# T01_Synth_Glove_v3_1.net
KiCad netlist of a schematic drawn in EAGLE
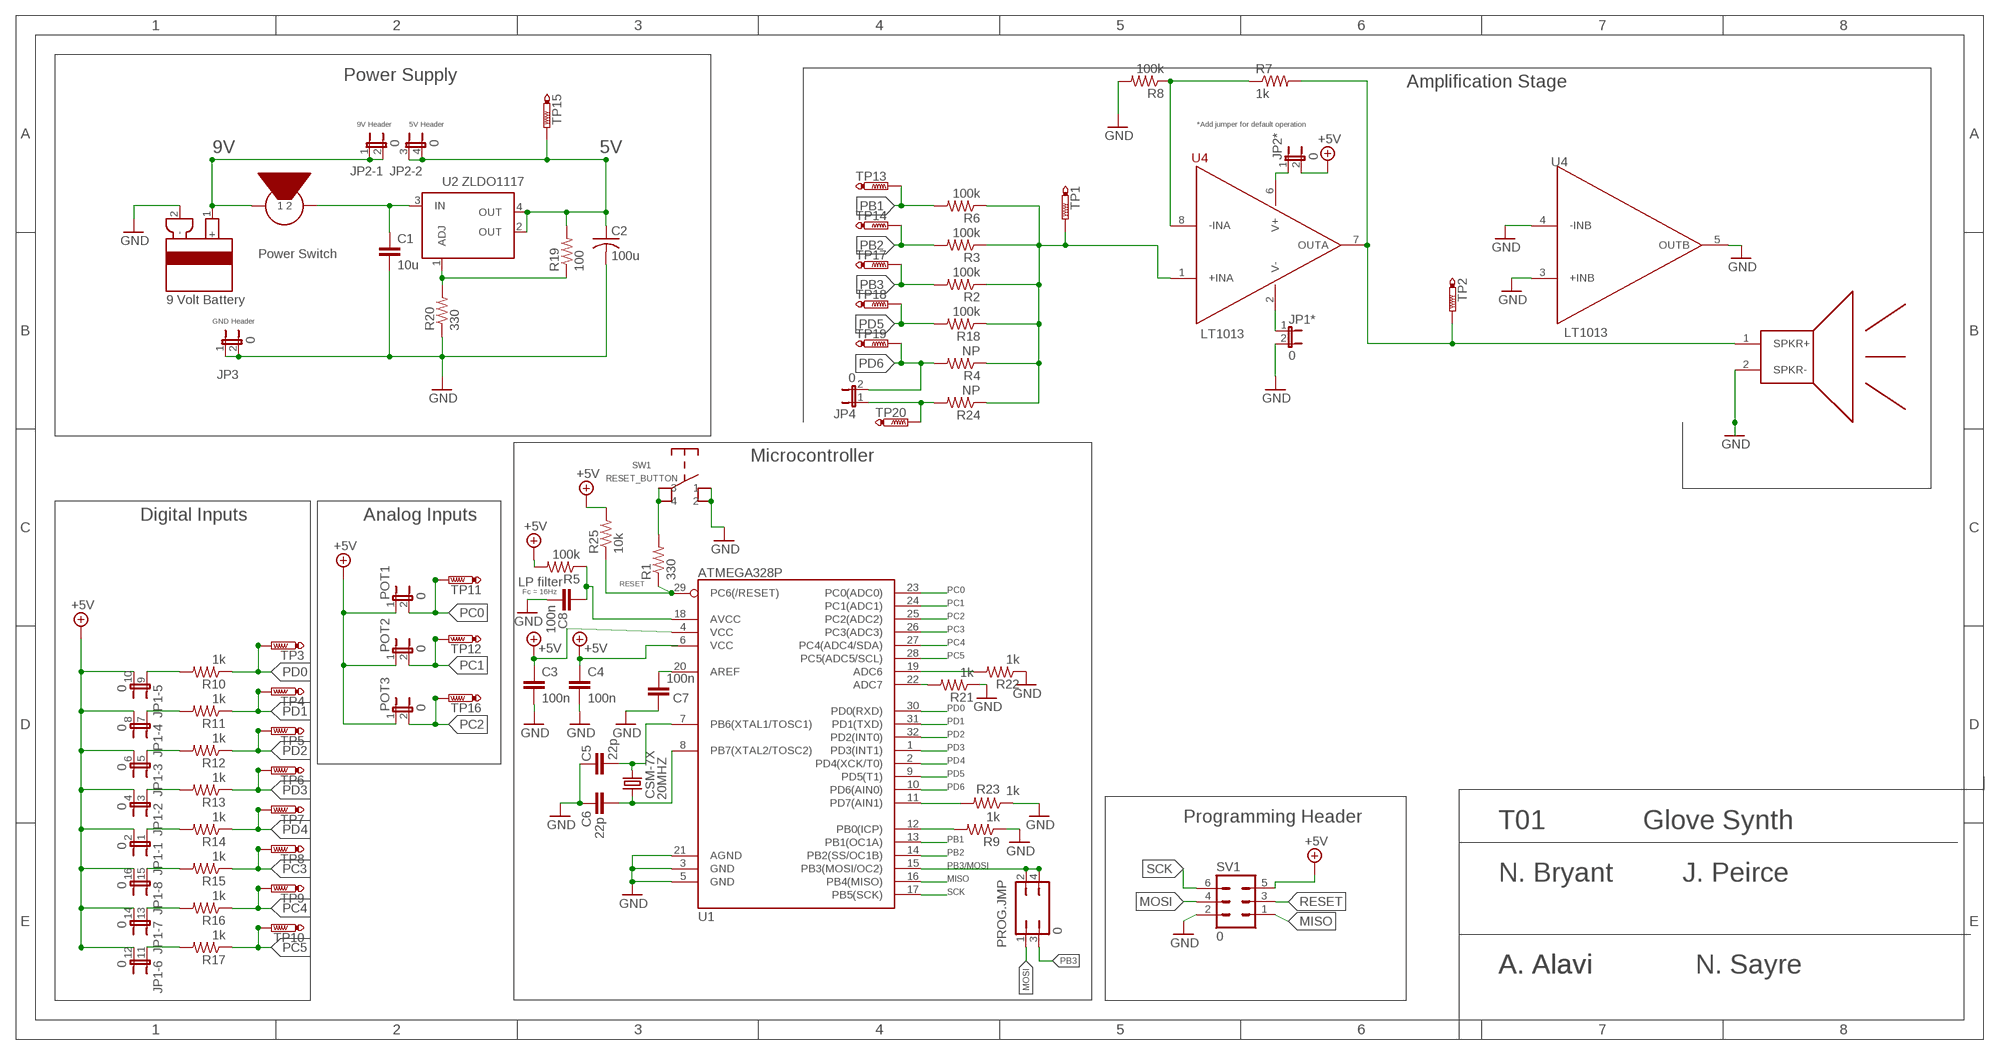
[diagram p0: schematic, sheet 1]

(export (version "E")
  (design (tool "Eeschema 10.0.6"))
  (components
    (comp (ref "20MHZ")
      (value "CSM-7X")
      (footprint "eagle-import:CSM-7X-DU")
      (libsource (lib "eagle-import") (part "CSM-7X-DU"))
    )
    (comp (ref "C1")
      (value "10u")
      (footprint "eagle-import:0603-CAP")
      (libsource (lib "eagle-import") (part "CAP0603-CAP"))
    )
    (comp (ref "C2")
      (value "100u")
      (footprint "eagle-import:C075-042X103")
      (libsource (lib "eagle-import") (part "C-US075-042X103"))
    )
    (comp (ref "C3")
      (value "100n")
      (footprint "eagle-import:0603-CAP")
      (libsource (lib "eagle-import") (part "CAP0603-CAP"))
    )
    (comp (ref "C4")
      (value "100n")
      (footprint "eagle-import:0603-CAP")
      (libsource (lib "eagle-import") (part "CAP0603-CAP"))
    )
    (comp (ref "C5")
      (value "22p")
      (footprint "eagle-import:0603-CAP")
      (libsource (lib "eagle-import") (part "CAP0603-CAP"))
    )
    (comp (ref "C6")
      (value "22p")
      (footprint "eagle-import:0603-CAP")
      (libsource (lib "eagle-import") (part "CAP0603-CAP"))
    )
    (comp (ref "C7")
      (value "100n")
      (footprint "eagle-import:0603-CAP")
      (libsource (lib "eagle-import") (part "CAP0603-CAP"))
    )
    (comp (ref "C8")
      (value "100n")
      (footprint "eagle-import:0603-CAP")
      (libsource (lib "eagle-import") (part "CAP0603-CAP"))
    )
    (comp (ref "JP1")
      (value "0")
      (footprint "eagle-import:JP8Q")
      (libsource (lib "eagle-import") (part "JP8QE"))
    )
    (comp (ref "JP1*")
      (value "0")
      (footprint "eagle-import:JP1")
      (libsource (lib "eagle-import") (part "JP1E"))
    )
    (comp (ref "JP2")
      (value "0")
      (footprint "eagle-import:JP2Q")
      (libsource (lib "eagle-import") (part "JP2QE"))
    )
    (comp (ref "JP2*")
      (value "0")
      (footprint "eagle-import:JP1")
      (libsource (lib "eagle-import") (part "JP1E"))
    )
    (comp (ref "JP3")
      (value "0")
      (footprint "eagle-import:JP1")
      (libsource (lib "eagle-import") (part "JP1E"))
    )
    (comp (ref "JP4")
      (value "0")
      (footprint "eagle-import:JP1")
      (libsource (lib "eagle-import") (part "JP1E"))
    )
    (comp (ref "POT1")
      (value "0")
      (footprint "eagle-import:JP1")
      (libsource (lib "eagle-import") (part "JP1E"))
    )
    (comp (ref "POT2")
      (value "0")
      (footprint "eagle-import:JP1")
      (libsource (lib "eagle-import") (part "JP1E"))
    )
    (comp (ref "POT3")
      (value "0")
      (footprint "eagle-import:JP1")
      (libsource (lib "eagle-import") (part "JP1E"))
    )
    (comp (ref "PROG.JMP")
      (value "0")
      (footprint "eagle-import:JP2Q")
      (libsource (lib "eagle-import") (part "JP2Q"))
    )
    (comp (ref "R1")
      (value "330")
      (footprint "eagle-import:0603-RES")
      (libsource (lib "eagle-import") (part "RESISTOR0603"))
    )
    (comp (ref "R2")
      (value "100k")
      (footprint "eagle-import:0603-RES")
      (libsource (lib "eagle-import") (part "RESISTOR0603"))
    )
    (comp (ref "R3")
      (value "100k")
      (footprint "eagle-import:0603-RES")
      (libsource (lib "eagle-import") (part "RESISTOR0603"))
    )
    (comp (ref "R4")
      (value "NP")
      (footprint "eagle-import:0603-RES")
      (libsource (lib "eagle-import") (part "RESISTOR0603"))
    )
    (comp (ref "R5")
      (value "100k")
      (footprint "eagle-import:0603-RES")
      (libsource (lib "eagle-import") (part "RESISTOR0603"))
    )
    (comp (ref "R6")
      (value "100k")
      (footprint "eagle-import:0603-RES")
      (libsource (lib "eagle-import") (part "RESISTOR0603"))
    )
    (comp (ref "R7")
      (value "1k")
      (footprint "eagle-import:0603-RES")
      (libsource (lib "eagle-import") (part "RESISTOR0603"))
    )
    (comp (ref "R8")
      (value "100k")
      (footprint "eagle-import:0603-RES")
      (libsource (lib "eagle-import") (part "RESISTOR0603"))
    )
    (comp (ref "R9")
      (value "1k")
      (footprint "eagle-import:0603-RES")
      (libsource (lib "eagle-import") (part "RESISTOR0603"))
    )
    (comp (ref "R10")
      (value "1k")
      (footprint "eagle-import:0603-RES")
      (libsource (lib "eagle-import") (part "RESISTOR0603"))
    )
    (comp (ref "R11")
      (value "1k")
      (footprint "eagle-import:0603-RES")
      (libsource (lib "eagle-import") (part "RESISTOR0603"))
    )
    (comp (ref "R12")
      (value "1k")
      (footprint "eagle-import:0603-RES")
      (libsource (lib "eagle-import") (part "RESISTOR0603"))
    )
    (comp (ref "R13")
      (value "1k")
      (footprint "eagle-import:0603-RES")
      (libsource (lib "eagle-import") (part "RESISTOR0603"))
    )
    (comp (ref "R14")
      (value "1k")
      (footprint "eagle-import:0603-RES")
      (libsource (lib "eagle-import") (part "RESISTOR0603"))
    )
    (comp (ref "R15")
      (value "1k")
      (footprint "eagle-import:0603-RES")
      (libsource (lib "eagle-import") (part "RESISTOR0603"))
    )
    (comp (ref "R16")
      (value "1k")
      (footprint "eagle-import:0603-RES")
      (libsource (lib "eagle-import") (part "RESISTOR0603"))
    )
    (comp (ref "R17")
      (value "1k")
      (footprint "eagle-import:0603-RES")
      (libsource (lib "eagle-import") (part "RESISTOR0603"))
    )
    (comp (ref "R18")
      (value "100k")
      (footprint "eagle-import:0603-RES")
      (libsource (lib "eagle-import") (part "RESISTOR0603"))
    )
    (comp (ref "R19")
      (value "100")
      (footprint "eagle-import:0603-RES")
      (libsource (lib "eagle-import") (part "RESISTOR0603"))
    )
    (comp (ref "R20")
      (value "330")
      (footprint "eagle-import:0603-RES")
      (libsource (lib "eagle-import") (part "RESISTOR0603"))
    )
    (comp (ref "R21")
      (value "1k")
      (footprint "eagle-import:0603-RES")
      (libsource (lib "eagle-import") (part "RESISTOR0603"))
    )
    (comp (ref "R22")
      (value "1k")
      (footprint "eagle-import:0603-RES")
      (libsource (lib "eagle-import") (part "RESISTOR0603"))
    )
    (comp (ref "R23")
      (value "1k")
      (footprint "eagle-import:0603-RES")
      (libsource (lib "eagle-import") (part "RESISTOR0603"))
    )
    (comp (ref "R24")
      (value "NP")
      (footprint "eagle-import:0603-RES")
      (libsource (lib "eagle-import") (part "RESISTOR0603"))
    )
    (comp (ref "R25")
      (value "10k")
      (footprint "eagle-import:0603-RES")
      (libsource (lib "eagle-import") (part "RESISTOR0603"))
    )
    (comp (ref "SV1")
      (value "0")
      (footprint "eagle-import:MA03-2")
      (libsource (lib "eagle-import") (part "MA03-2"))
    )
    (comp (ref "SW1")
      (value "RESET_BUTTON")
      (footprint "eagle-import:RESET_BUTTON")
      (libsource (lib "eagle-import") (part "RESET_BUTTON"))
    )
    (comp (ref "TP1")
      (value "PTR1B2,54")
      (footprint "eagle-import:B2,54")
      (libsource (lib "eagle-import") (part "PTR1B2,54"))
    )
    (comp (ref "TP2")
      (value "PTR1B2,54")
      (footprint "eagle-import:B2,54")
      (libsource (lib "eagle-import") (part "PTR1B2,54"))
    )
    (comp (ref "TP3")
      (value "PTR1B2,54")
      (footprint "eagle-import:B2,54")
      (libsource (lib "eagle-import") (part "PTR1B2,54"))
    )
    (comp (ref "TP4")
      (value "PTR1B2,54")
      (footprint "eagle-import:B2,54")
      (libsource (lib "eagle-import") (part "PTR1B2,54"))
    )
    (comp (ref "TP5")
      (value "PTR1B2,54")
      (footprint "eagle-import:B2,54")
      (libsource (lib "eagle-import") (part "PTR1B2,54"))
    )
    (comp (ref "TP6")
      (value "PTR1B2,54")
      (footprint "eagle-import:B2,54")
      (libsource (lib "eagle-import") (part "PTR1B2,54"))
    )
    (comp (ref "TP7")
      (value "PTR1B2,54")
      (footprint "eagle-import:B2,54")
      (libsource (lib "eagle-import") (part "PTR1B2,54"))
    )
    (comp (ref "TP8")
      (value "PTR1B2,54")
      (footprint "eagle-import:B2,54")
      (libsource (lib "eagle-import") (part "PTR1B2,54"))
    )
    (comp (ref "TP9")
      (value "PTR1B2,54")
      (footprint "eagle-import:B2,54")
      (libsource (lib "eagle-import") (part "PTR1B2,54"))
    )
    (comp (ref "TP10")
      (value "PTR1B2,54")
      (footprint "eagle-import:B2,54")
      (libsource (lib "eagle-import") (part "PTR1B2,54"))
    )
    (comp (ref "TP11")
      (value "PTR1B2,54")
      (footprint "eagle-import:B2,54")
      (libsource (lib "eagle-import") (part "PTR1B2,54"))
    )
    (comp (ref "TP12")
      (value "PTR1B2,54")
      (footprint "eagle-import:B2,54")
      (libsource (lib "eagle-import") (part "PTR1B2,54"))
    )
    (comp (ref "TP13")
      (value "PTR1B2,54")
      (footprint "eagle-import:B2,54")
      (libsource (lib "eagle-import") (part "PTR1B2,54"))
    )
    (comp (ref "TP14")
      (value "PTR1B2,54")
      (footprint "eagle-import:B2,54")
      (libsource (lib "eagle-import") (part "PTR1B2,54"))
    )
    (comp (ref "TP15")
      (value "PTR1B2,54")
      (footprint "eagle-import:B2,54")
      (libsource (lib "eagle-import") (part "PTR1B2,54"))
    )
    (comp (ref "TP16")
      (value "PTR1B2,54")
      (footprint "eagle-import:B2,54")
      (libsource (lib "eagle-import") (part "PTR1B2,54"))
    )
    (comp (ref "TP17")
      (value "PTR1B2,54")
      (footprint "eagle-import:B2,54")
      (libsource (lib "eagle-import") (part "PTR1B2,54"))
    )
    (comp (ref "TP18")
      (value "PTR1B2,54")
      (footprint "eagle-import:B2,54")
      (libsource (lib "eagle-import") (part "PTR1B2,54"))
    )
    (comp (ref "TP19")
      (value "PTR1B2,54")
      (footprint "eagle-import:B2,54")
      (libsource (lib "eagle-import") (part "PTR1B2,54"))
    )
    (comp (ref "TP20")
      (value "PTR1B2,54")
      (footprint "eagle-import:B2,54")
      (libsource (lib "eagle-import") (part "PTR1B2,54"))
    )
    (comp (ref "U$1")
      (value "SPEAKER")
      (footprint "eagle-import:JP1")
      (libsource (lib "eagle-import") (part "SPEAKER"))
    )
    (comp (ref "U$7")
      (value "POWER_SWITCH")
      (footprint "eagle-import:JP1")
      (libsource (lib "eagle-import") (part "POWER_SWITCH"))
    )
    (comp (ref "U$8")
      (value "9VOLTBATTERY")
      (footprint "eagle-import:JP1")
      (libsource (lib "eagle-import") (part "9VOLTBATTERY"))
    )
    (comp (ref "U1")
      (value "ATMEGA328P")
      (footprint "eagle-import:TQFP32-08")
      (libsource (lib "eagle-import") (part "ATMEGA328_SMT"))
    )
    (comp (ref "U2")
      (value "ZLDO1117")
      (footprint "eagle-import:SOT223")
      (libsource (lib "eagle-import") (part "ZLDO1117"))
    )
    (comp (ref "U4")
      (value "LT1013")
      (footprint "eagle-import:SO08")
      (libsource (lib "eagle-import") (part "LT1013"))
    )
  )
  (nets
    (net (code "1") (name "+5V") (class "Default")
      (node (ref "C3") (pin "1") (pinfunction "1_1") (pintype "passive"))
      (node (ref "C4") (pin "1") (pinfunction "1_1") (pintype "passive"))
      (node (ref "JP1") (pin "10") (pinfunction "2_10") (pintype "passive"))
      (node (ref "JP1") (pin "12") (pinfunction "2_12") (pintype "passive"))
      (node (ref "JP1") (pin "14") (pinfunction "2_14") (pintype "passive"))
      (node (ref "JP1") (pin "16") (pinfunction "2_16") (pintype "passive"))
      (node (ref "JP1") (pin "2") (pinfunction "2_2") (pintype "passive"))
      (node (ref "JP1") (pin "4") (pinfunction "2_4") (pintype "passive"))
      (node (ref "JP1") (pin "6") (pinfunction "2_6") (pintype "passive"))
      (node (ref "JP1") (pin "8") (pinfunction "2_8") (pintype "passive"))
      (node (ref "JP2*") (pin "2") (pinfunction "2_2") (pintype "passive"))
      (node (ref "POT1") (pin "1") (pinfunction "1_1") (pintype "passive"))
      (node (ref "POT2") (pin "1") (pinfunction "1_1") (pintype "passive"))
      (node (ref "POT3") (pin "1") (pinfunction "1_1") (pintype "passive"))
      (node (ref "R25") (pin "2") (pinfunction "2_2") (pintype "passive"))
      (node (ref "R5") (pin "2") (pinfunction "2_2") (pintype "passive"))
      (node (ref "SV1") (pin "5") (pinfunction "5_5") (pintype "passive"))
      (node (ref "U1") (pin "4") (pinfunction "VCC_4") (pintype "bidirectional"))
    )
    (net (code "2") (name "/5V") (class "Default")
      (node (ref "C2") (pin "1") (pinfunction "1_1") (pintype "passive"))
      (node (ref "JP2") (pin "3") (pinfunction "1_3") (pintype "passive"))
      (node (ref "JP2") (pin "4") (pinfunction "2_4") (pintype "passive"))
      (node (ref "R19") (pin "2") (pinfunction "2_2") (pintype "passive"))
      (node (ref "TP15") (pin "TP") (pinfunction "TP_TP") (pintype "input"))
      (node (ref "U2") (pin "2") (pinfunction "OUT_2") (pintype "bidirectional"))
      (node (ref "U2") (pin "4") (pinfunction "OUT_4") (pintype "bidirectional"))
    )
    (net (code "3") (name "/9V") (class "Default")
      (node (ref "JP2") (pin "1") (pinfunction "1_1") (pintype "passive"))
      (node (ref "JP2") (pin "2") (pinfunction "2_2") (pintype "passive"))
      (node (ref "U$7") (pin "1") (pinfunction "1_1") (pintype "bidirectional"))
      (node (ref "U$8") (pin "1") (pinfunction "+_1") (pintype "bidirectional"))
    )
    (net (code "4") (name "/PB3{slash}MOSI") (class "Default")
      (node (ref "PROG.JMP") (pin "2") (pinfunction "2_2") (pintype "passive"))
      (node (ref "PROG.JMP") (pin "4") (pinfunction "4_4") (pintype "passive"))
      (node (ref "U1") (pin "15") (pinfunction "PB3(MOSI/OC2)_15") (pintype "bidirectional"))
    )
    (net (code "5") (name "GND") (class "Default")
      (node (ref "C1") (pin "2") (pinfunction "2_2") (pintype "passive"))
      (node (ref "C2") (pin "2") (pinfunction "2_2") (pintype "passive"))
      (node (ref "C3") (pin "2") (pinfunction "2_2") (pintype "passive"))
      (node (ref "C4") (pin "2") (pinfunction "2_2") (pintype "passive"))
      (node (ref "C5") (pin "2") (pinfunction "2_2") (pintype "passive"))
      (node (ref "C6") (pin "2") (pinfunction "2_2") (pintype "passive"))
      (node (ref "C7") (pin "2") (pinfunction "2_2") (pintype "passive"))
      (node (ref "C8") (pin "2") (pinfunction "2_2") (pintype "passive"))
      (node (ref "JP1*") (pin "2") (pinfunction "2_2") (pintype "passive"))
      (node (ref "JP3") (pin "1") (pinfunction "1_1") (pintype "passive"))
      (node (ref "JP3") (pin "2") (pinfunction "2_2") (pintype "passive"))
      (node (ref "R20") (pin "1") (pinfunction "1_1") (pintype "passive"))
      (node (ref "R21") (pin "1") (pinfunction "1_1") (pintype "passive"))
      (node (ref "R22") (pin "1") (pinfunction "1_1") (pintype "passive"))
      (node (ref "R23") (pin "1") (pinfunction "1_1") (pintype "passive"))
      (node (ref "R8") (pin "2") (pinfunction "2_2") (pintype "passive"))
      (node (ref "R9") (pin "1") (pinfunction "1_1") (pintype "passive"))
      (node (ref "SV1") (pin "2") (pinfunction "2_2") (pintype "passive"))
      (node (ref "SW1") (pin "1") (pinfunction "1_1") (pintype "bidirectional"))
      (node (ref "SW1") (pin "2") (pinfunction "2_2") (pintype "bidirectional"))
      (node (ref "U$1") (pin "2") (pinfunction "SPKR-_2") (pintype "bidirectional"))
      (node (ref "U$8") (pin "2") (pinfunction "-_2") (pintype "bidirectional"))
      (node (ref "U1") (pin "21") (pinfunction "AGND_21") (pintype "bidirectional"))
      (node (ref "U1") (pin "3") (pinfunction "GND_3") (pintype "bidirectional"))
      (node (ref "U1") (pin "5") (pinfunction "GND_5") (pintype "bidirectional"))
      (node (ref "U4") (pin "3") (pinfunction "+INB_3") (pintype "bidirectional"))
      (node (ref "U4") (pin "4") (pinfunction "-INB_4") (pintype "bidirectional"))
      (node (ref "U4") (pin "5") (pinfunction "OUTB_5") (pintype "bidirectional"))
    )
    (net (code "6") (name "MISO") (class "Default")
      (node (ref "SV1") (pin "1") (pinfunction "1_1") (pintype "passive"))
      (node (ref "U1") (pin "16") (pinfunction "PB4(MISO)_16") (pintype "bidirectional"))
    )
    (net (code "7") (name "MOSI") (class "Default")
      (node (ref "PROG.JMP") (pin "1") (pinfunction "1_1") (pintype "passive"))
      (node (ref "SV1") (pin "4") (pinfunction "4_4") (pintype "passive"))
    )
    (net (code "8") (name "Net-(JP1-Pad1)") (class "Default")
      (node (ref "JP1") (pin "1") (pinfunction "1_1") (pintype "passive"))
      (node (ref "R14") (pin "2") (pinfunction "2_2") (pintype "passive"))
    )
    (net (code "9") (name "Net-(JP1B-1)") (class "Default")
      (node (ref "JP1") (pin "3") (pinfunction "1_3") (pintype "passive"))
      (node (ref "R13") (pin "2") (pinfunction "2_2") (pintype "passive"))
    )
    (net (code "10") (name "Net-(JP1C-1)") (class "Default")
      (node (ref "JP1") (pin "5") (pinfunction "1_5") (pintype "passive"))
      (node (ref "R12") (pin "2") (pinfunction "2_2") (pintype "passive"))
    )
    (net (code "11") (name "Net-(JP1D-1)") (class "Default")
      (node (ref "JP1") (pin "7") (pinfunction "1_7") (pintype "passive"))
      (node (ref "R11") (pin "2") (pinfunction "2_2") (pintype "passive"))
    )
    (net (code "12") (name "Net-(JP1E-1)") (class "Default")
      (node (ref "JP1") (pin "9") (pinfunction "1_9") (pintype "passive"))
      (node (ref "R10") (pin "2") (pinfunction "2_2") (pintype "passive"))
    )
    (net (code "13") (name "Net-(JP1F-1)") (class "Default")
      (node (ref "JP1") (pin "11") (pinfunction "1_11") (pintype "passive"))
      (node (ref "R17") (pin "2") (pinfunction "2_2") (pintype "passive"))
    )
    (net (code "14") (name "Net-(JP1G-1)") (class "Default")
      (node (ref "JP1") (pin "13") (pinfunction "1_13") (pintype "passive"))
      (node (ref "R16") (pin "2") (pinfunction "2_2") (pintype "passive"))
    )
    (net (code "15") (name "Net-(JP1H-1)") (class "Default")
      (node (ref "JP1") (pin "15") (pinfunction "1_15") (pintype "passive"))
      (node (ref "R15") (pin "2") (pinfunction "2_2") (pintype "passive"))
    )
    (net (code "16") (name "Net-(JP4-Pad1)") (class "Default")
      (node (ref "JP4") (pin "1") (pinfunction "1_1") (pintype "passive"))
      (node (ref "R24") (pin "2") (pinfunction "2_2") (pintype "passive"))
      (node (ref "TP20") (pin "TP") (pinfunction "TP_TP") (pintype "input"))
    )
    (net (code "17") (name "Net-(R1-Pad2)") (class "Default")
      (node (ref "R1") (pin "2") (pinfunction "2_2") (pintype "passive"))
      (node (ref "SW1") (pin "3") (pinfunction "3_3") (pintype "bidirectional"))
      (node (ref "SW1") (pin "4") (pinfunction "4_4") (pintype "bidirectional"))
    )
    (net (code "18") (name "Net-(U$1-SPKR+)") (class "Default")
      (node (ref "R7") (pin "2") (pinfunction "2_2") (pintype "passive"))
      (node (ref "TP2") (pin "TP") (pinfunction "TP_TP") (pintype "input"))
      (node (ref "U$1") (pin "1") (pinfunction "SPKR+_1") (pintype "bidirectional"))
      (node (ref "U4") (pin "7") (pinfunction "OUTA_7") (pintype "bidirectional"))
    )
    (net (code "19") (name "Net-(U1-ADC6)") (class "Default")
      (node (ref "R22") (pin "2") (pinfunction "2_2") (pintype "passive"))
      (node (ref "U1") (pin "19") (pinfunction "ADC6_19") (pintype "bidirectional"))
    )
    (net (code "20") (name "Net-(U1-ADC7)") (class "Default")
      (node (ref "R21") (pin "2") (pinfunction "2_2") (pintype "passive"))
      (node (ref "U1") (pin "22") (pinfunction "ADC7_22") (pintype "bidirectional"))
    )
    (net (code "21") (name "Net-(U1-AREF)") (class "Default")
      (node (ref "C7") (pin "1") (pinfunction "1_1") (pintype "passive"))
      (node (ref "U1") (pin "20") (pinfunction "AREF_20") (pintype "bidirectional"))
    )
    (net (code "22") (name "Net-(U1-AVCC)") (class "Default")
      (node (ref "C8") (pin "1") (pinfunction "1_1") (pintype "passive"))
      (node (ref "R5") (pin "1") (pinfunction "1_1") (pintype "passive"))
      (node (ref "U1") (pin "18") (pinfunction "AVCC_18") (pintype "bidirectional"))
    )
    (net (code "23") (name "Net-(U1-PB0(ICP))") (class "Default")
      (node (ref "R9") (pin "2") (pinfunction "2_2") (pintype "passive"))
      (node (ref "U1") (pin "12") (pinfunction "PB0(ICP)_12") (pintype "bidirectional"))
    )
    (net (code "24") (name "Net-(U1-PB6(XTAL1{slash}TOSC1))") (class "Default")
      (node (ref "20MHZ") (pin "1") (pinfunction "1_1") (pintype "passive"))
      (node (ref "C5") (pin "1") (pinfunction "1_1") (pintype "passive"))
      (node (ref "U1") (pin "7") (pinfunction "PB6(XTAL1/TOSC1)_7") (pintype "bidirectional"))
    )
    (net (code "25") (name "Net-(U1-PB7(XTAL2{slash}TOSC2))") (class "Default")
      (node (ref "20MHZ") (pin "2") (pinfunction "2_2") (pintype "passive"))
      (node (ref "C6") (pin "1") (pinfunction "1_1") (pintype "passive"))
      (node (ref "U1") (pin "8") (pinfunction "PB7(XTAL2/TOSC2)_8") (pintype "bidirectional"))
    )
    (net (code "26") (name "Net-(U1-PD7(AIN1))") (class "Default")
      (node (ref "R23") (pin "2") (pinfunction "2_2") (pintype "passive"))
      (node (ref "U1") (pin "11") (pinfunction "PD7(AIN1)_11") (pintype "bidirectional"))
    )
    (net (code "27") (name "Net-(U2-ADJ)") (class "Default")
      (node (ref "R19") (pin "1") (pinfunction "1_1") (pintype "passive"))
      (node (ref "R20") (pin "2") (pinfunction "2_2") (pintype "passive"))
      (node (ref "U2") (pin "1") (pinfunction "ADJ_1") (pintype "bidirectional"))
    )
    (net (code "28") (name "Net-(U2-IN)") (class "Default")
      (node (ref "C1") (pin "1") (pinfunction "1_1") (pintype "passive"))
      (node (ref "U$7") (pin "2") (pinfunction "2_2") (pintype "bidirectional"))
      (node (ref "U2") (pin "3") (pinfunction "IN_3") (pintype "bidirectional"))
    )
    (net (code "29") (name "Net-(U4-+INA)") (class "Default")
      (node (ref "R18") (pin "1") (pinfunction "1_1") (pintype "passive"))
      (node (ref "R2") (pin "1") (pinfunction "1_1") (pintype "passive"))
      (node (ref "R24") (pin "1") (pinfunction "1_1") (pintype "passive"))
      (node (ref "R3") (pin "1") (pinfunction "1_1") (pintype "passive"))
      (node (ref "R4") (pin "1") (pinfunction "1_1") (pintype "passive"))
      (node (ref "R6") (pin "1") (pinfunction "1_1") (pintype "passive"))
      (node (ref "TP1") (pin "TP") (pinfunction "TP_TP") (pintype "input"))
      (node (ref "U4") (pin "1") (pinfunction "+INA_1") (pintype "bidirectional"))
    )
    (net (code "30") (name "Net-(U4--INA)") (class "Default")
      (node (ref "R7") (pin "1") (pinfunction "1_1") (pintype "passive"))
      (node (ref "R8") (pin "1") (pinfunction "1_1") (pintype "passive"))
      (node (ref "U4") (pin "8") (pinfunction "-INA_8") (pintype "bidirectional"))
    )
    (net (code "31") (name "Net-(U4-V+)") (class "Default")
      (node (ref "JP2*") (pin "1") (pinfunction "1_1") (pintype "passive"))
      (node (ref "U4") (pin "6") (pinfunction "V+_6") (pintype "power_in"))
    )
    (net (code "32") (name "Net-(U4-V-)") (class "Default")
      (node (ref "JP1*") (pin "1") (pinfunction "1_1") (pintype "passive"))
      (node (ref "U4") (pin "2") (pinfunction "V-_2") (pintype "power_in"))
    )
    (net (code "33") (name "PB1") (class "Default")
      (node (ref "R6") (pin "2") (pinfunction "2_2") (pintype "passive"))
      (node (ref "TP13") (pin "TP") (pinfunction "TP_TP") (pintype "input"))
      (node (ref "U1") (pin "13") (pinfunction "PB1(OC1A)_13") (pintype "bidirectional"))
    )
    (net (code "34") (name "PB2") (class "Default")
      (node (ref "R3") (pin "2") (pinfunction "2_2") (pintype "passive"))
      (node (ref "TP14") (pin "TP") (pinfunction "TP_TP") (pintype "input"))
      (node (ref "U1") (pin "14") (pinfunction "PB2(SS/OC1B)_14") (pintype "bidirectional"))
    )
    (net (code "35") (name "PB3") (class "Default")
      (node (ref "PROG.JMP") (pin "3") (pinfunction "3_3") (pintype "passive"))
      (node (ref "R2") (pin "2") (pinfunction "2_2") (pintype "passive"))
      (node (ref "TP17") (pin "TP") (pinfunction "TP_TP") (pintype "input"))
    )
    (net (code "36") (name "PC0") (class "Default")
      (node (ref "POT1") (pin "2") (pinfunction "2_2") (pintype "passive"))
      (node (ref "TP11") (pin "TP") (pinfunction "TP_TP") (pintype "input"))
      (node (ref "U1") (pin "23") (pinfunction "PC0(ADC0)_23") (pintype "bidirectional"))
    )
    (net (code "37") (name "PC1") (class "Default")
      (node (ref "POT2") (pin "2") (pinfunction "2_2") (pintype "passive"))
      (node (ref "TP12") (pin "TP") (pinfunction "TP_TP") (pintype "input"))
      (node (ref "U1") (pin "24") (pinfunction "PC1(ADC1)_24") (pintype "bidirectional"))
    )
    (net (code "38") (name "PC2") (class "Default")
      (node (ref "POT3") (pin "2") (pinfunction "2_2") (pintype "passive"))
      (node (ref "TP16") (pin "TP") (pinfunction "TP_TP") (pintype "input"))
      (node (ref "U1") (pin "25") (pinfunction "PC2(ADC2)_25") (pintype "bidirectional"))
    )
    (net (code "39") (name "PC3") (class "Default")
      (node (ref "R15") (pin "1") (pinfunction "1_1") (pintype "passive"))
      (node (ref "TP8") (pin "TP") (pinfunction "TP_TP") (pintype "input"))
      (node (ref "U1") (pin "26") (pinfunction "PC3(ADC3)_26") (pintype "bidirectional"))
    )
    (net (code "40") (name "PC4") (class "Default")
      (node (ref "R16") (pin "1") (pinfunction "1_1") (pintype "passive"))
      (node (ref "TP9") (pin "TP") (pinfunction "TP_TP") (pintype "input"))
      (node (ref "U1") (pin "27") (pinfunction "PC4(ADC4/SDA)_27") (pintype "bidirectional"))
    )
    (net (code "41") (name "PC5") (class "Default")
      (node (ref "R17") (pin "1") (pinfunction "1_1") (pintype "passive"))
      (node (ref "TP10") (pin "TP") (pinfunction "TP_TP") (pintype "input"))
      (node (ref "U1") (pin "28") (pinfunction "PC5(ADC5/SCL)_28") (pintype "bidirectional"))
    )
    (net (code "42") (name "PD0") (class "Default")
      (node (ref "R10") (pin "1") (pinfunction "1_1") (pintype "passive"))
      (node (ref "TP3") (pin "TP") (pinfunction "TP_TP") (pintype "input"))
      (node (ref "U1") (pin "30") (pinfunction "PD0(RXD)_30") (pintype "bidirectional"))
    )
    (net (code "43") (name "PD1") (class "Default")
      (node (ref "R11") (pin "1") (pinfunction "1_1") (pintype "passive"))
      (node (ref "TP4") (pin "TP") (pinfunction "TP_TP") (pintype "input"))
      (node (ref "U1") (pin "31") (pinfunction "PD1(TXD)_31") (pintype "bidirectional"))
    )
    (net (code "44") (name "PD2") (class "Default")
      (node (ref "R12") (pin "1") (pinfunction "1_1") (pintype "passive"))
      (node (ref "TP5") (pin "TP") (pinfunction "TP_TP") (pintype "input"))
      (node (ref "U1") (pin "32") (pinfunction "PD2(INT0)_32") (pintype "bidirectional"))
    )
    (net (code "45") (name "PD3") (class "Default")
      (node (ref "R13") (pin "1") (pinfunction "1_1") (pintype "passive"))
      (node (ref "TP6") (pin "TP") (pinfunction "TP_TP") (pintype "input"))
      (node (ref "U1") (pin "1") (pinfunction "PD3(INT1)_1") (pintype "bidirectional"))
    )
    (net (code "46") (name "PD4") (class "Default")
      (node (ref "R14") (pin "1") (pinfunction "1_1") (pintype "passive"))
      (node (ref "TP7") (pin "TP") (pinfunction "TP_TP") (pintype "input"))
      (node (ref "U1") (pin "2") (pinfunction "PD4(XCK/T0)_2") (pintype "bidirectional"))
    )
    (net (code "47") (name "PD5") (class "Default")
      (node (ref "R18") (pin "2") (pinfunction "2_2") (pintype "passive"))
      (node (ref "TP18") (pin "TP") (pinfunction "TP_TP") (pintype "input"))
      (node (ref "U1") (pin "9") (pinfunction "PD5(T1)_9") (pintype "bidirectional"))
    )
    (net (code "48") (name "PD6") (class "Default")
      (node (ref "JP4") (pin "2") (pinfunction "2_2") (pintype "passive"))
      (node (ref "R4") (pin "2") (pinfunction "2_2") (pintype "passive"))
      (node (ref "TP19") (pin "TP") (pinfunction "TP_TP") (pintype "input"))
      (node (ref "U1") (pin "10") (pinfunction "PD6(AIN0)_10") (pintype "bidirectional"))
    )
    (net (code "49") (name "RESET") (class "Default")
      (node (ref "R1") (pin "1") (pinfunction "1_1") (pintype "passive"))
      (node (ref "R25") (pin "1") (pinfunction "1_1") (pintype "passive"))
      (node (ref "SV1") (pin "3") (pinfunction "3_3") (pintype "passive"))
      (node (ref "U1") (pin "29") (pinfunction "PC6(/RESET)_29") (pintype "bidirectional"))
    )
    (net (code "50") (name "SCK") (class "Default")
      (node (ref "SV1") (pin "6") (pinfunction "6_6") (pintype "passive"))
      (node (ref "U1") (pin "17") (pinfunction "PB5(SCK)_17") (pintype "bidirectional"))
    )
    (net (code "51") (name "unconnected-(U1-VCC-Pad6)") (class "Default")
      (node (ref "U1") (pin "6") (pinfunction "VCC_6") (pintype "bidirectional"))
    )
  )
)
